# analog_lvb_sense.net
KiCad netlist of a schematic drawn in Altium Designer
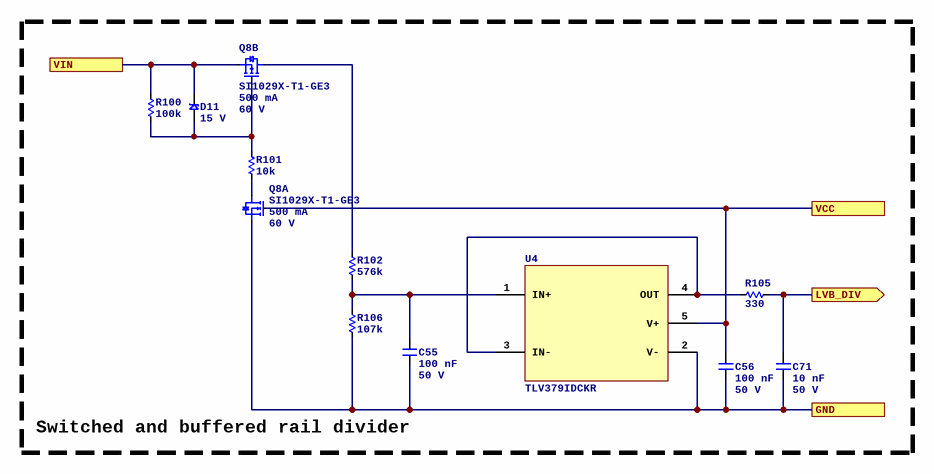
[diagram p0: analog_lvb_sense.SchDoc]

(export (version "E")
  (design (tool "Eeschema 10.0.6"))
  (components
    (comp (ref "C55")
      (value "CL05B104KB54PNC")
      (footprint "C0402")
      (fields
        (field (name "CAPACITANCE") "100 nF")
        (field (name "MANUFACTURER") "Samsung Electro-Mechanics")
        (field (name "VOLTAGE RATING") "50 V")
      )
      (libsource (lib "database") (part "__template_cap"))
    )
    (comp (ref "C56")
      (value "CL05B104KB54PNC")
      (footprint "C0402")
      (fields
        (field (name "CAPACITANCE") "100 nF")
        (field (name "MANUFACTURER") "Samsung Electro-Mechanics")
        (field (name "VOLTAGE RATING") "50 V")
      )
      (libsource (lib "database") (part "__template_cap"))
    )
    (comp (ref "C71")
      (value "CL05B103KB5NNNC")
      (footprint "C0402")
      (fields
        (field (name "CAPACITANCE") "10 nF")
        (field (name "MANUFACTURER") "Samsung Electro-Mechanics")
        (field (name "VOLTAGE RATING") "50 V")
      )
      (libsource (lib "database") (part "__template_cap"))
    )
    (comp (ref "D11")
      (value "MM3Z15VC")
      (footprint "SOD323")
      (description "DIODE ZENER 15V 200MW SOD")
      (fields (field (name "MANUFACTURER") "onsemi") (field (name "VR") "15 V"))
      (libsource (lib "database") (part "__template_diode_zener"))
    )
    (comp (ref "Q8")
      (value "SI1029X-T1-GE3")
      (footprint "6SOT563")
      (fields
        (field (name "MANUFACTURER") "Vishay Siliconix")
        (field (name "CURRENT") "500 mA")
        (field (name "VOLTAGE") "60 V")
      )
      (libsource (lib "database") (part "SI1029X-T1-GE3"))
    )
    (comp (ref "R100")
      (value "100k")
      (footprint "R0402")
      (fields
        (field (name "TOLERANCE") "1%")
        (field (name "MANUFACTURER PART NUMBER") "0402WGF1003TCE")
        (field (name "MANUFACTURER") "UNI-ROYAL(Uniroyal Elec)")
      )
      (libsource (lib "database") (part "__template_resistor"))
    )
    (comp (ref "R101")
      (value "10k")
      (footprint "R0402")
      (fields
        (field (name "TOLERANCE") "1%")
        (field (name "MANUFACTURER PART NUMBER") "0402WGF1002TCE")
        (field (name "MANUFACTURER") "UNI-ROYAL(Uniroyal Elec)")
      )
      (libsource (lib "database") (part "__template_resistor"))
    )
    (comp (ref "R102")
      (value "576k")
      (footprint "R0402")
      (fields
        (field (name "MANUFACTURER PART NUMBER") "0402WGF5763TCE")
        (field (name "MANUFACTURER") "UNI-ROYAL(Uniroyal Elec)")
        (field (name "TOLERANCE") "1%")
      )
      (libsource (lib "database") (part "__template_resistor"))
    )
    (comp (ref "R105")
      (value "330")
      (footprint "R0402")
      (fields
        (field (name "TOLERANCE") "1%")
        (field (name "MANUFACTURER PART NUMBER") "0402WGF3300TCE")
        (field (name "MANUFACTURER") "UNI-ROYAL(Uniroyal Elec)")
      )
      (libsource (lib "database") (part "__template_resistor"))
    )
    (comp (ref "R106")
      (value "107k")
      (footprint "R0402")
      (fields
        (field (name "MANUFACTURER PART NUMBER") "0402WGF1073TCE")
        (field (name "MANUFACTURER") "UNI-ROYAL(Uniroyal Elec)")
        (field (name "TOLERANCE") "1%")
      )
      (libsource (lib "database") (part "__template_resistor"))
    )
    (comp (ref "U4")
      (value "TLV379IDCKR")
      (footprint "5SC70")
      (fields (field (name "MANUFACTURER") "Texas Instruments"))
      (libsource (lib "database") (part "TLV379IDCKR"))
    )
  )
  (nets
    (net (code "1") (name "/GND") (class "Default")
      (node (ref "C55") (pin "2") (pintype "passive"))
      (node (ref "C56") (pin "2") (pintype "passive"))
      (node (ref "C71") (pin "2") (pintype "passive"))
      (node (ref "Q8") (pin "1") (pintype "passive"))
      (node (ref "R106") (pin "1") (pintype "passive"))
      (node (ref "U4") (pin "2") (pinfunction "V-_2") (pintype "passive"))
    )
    (net (code "2") (name "/LVB_DIV") (class "Default")
      (node (ref "C71") (pin "1") (pintype "passive"))
      (node (ref "R105") (pin "2") (pintype "passive"))
    )
    (net (code "3") (name "/VCC") (class "Default")
      (node (ref "C56") (pin "1") (pintype "passive"))
      (node (ref "Q8") (pin "2") (pintype "passive"))
      (node (ref "U4") (pin "5") (pinfunction "V+_5") (pintype "passive"))
    )
    (net (code "4") (name "/VIN") (class "Default")
      (node (ref "D11") (pin "2") (pintype "passive"))
      (node (ref "Q8") (pin "4") (pintype "passive"))
      (node (ref "R100") (pin "1") (pintype "passive"))
    )
    (net (code "5") (name "Net-(D11-Pad1)") (class "Default")
      (node (ref "D11") (pin "1") (pintype "passive"))
      (node (ref "Q8") (pin "5") (pintype "passive"))
      (node (ref "R100") (pin "2") (pintype "passive"))
      (node (ref "R101") (pin "1") (pintype "passive"))
    )
    (net (code "6") (name "Net-(Q8-Pad3)") (class "Default")
      (node (ref "Q8") (pin "3") (pintype "passive"))
      (node (ref "R102") (pin "2") (pintype "passive"))
    )
    (net (code "7") (name "Net-(Q8-Pad6)") (class "Default")
      (node (ref "Q8") (pin "6") (pintype "passive"))
      (node (ref "R101") (pin "2") (pintype "passive"))
    )
    (net (code "8") (name "Net-(U4-IN+)") (class "Default")
      (node (ref "C55") (pin "1") (pintype "passive"))
      (node (ref "R102") (pin "1") (pintype "passive"))
      (node (ref "R106") (pin "2") (pintype "passive"))
      (node (ref "U4") (pin "1") (pinfunction "IN+_1") (pintype "passive"))
    )
    (net (code "9") (name "Net-(U4-IN-)") (class "Default")
      (node (ref "R105") (pin "1") (pintype "passive"))
      (node (ref "U4") (pin "3") (pinfunction "IN-_3") (pintype "passive"))
      (node (ref "U4") (pin "4") (pinfunction "OUT_4") (pintype "passive"))
    )
  )
)
